# Adafruit_TSSP77038_IR_Demodulator_Breako.net
KiCad netlist of a schematic drawn in EAGLE
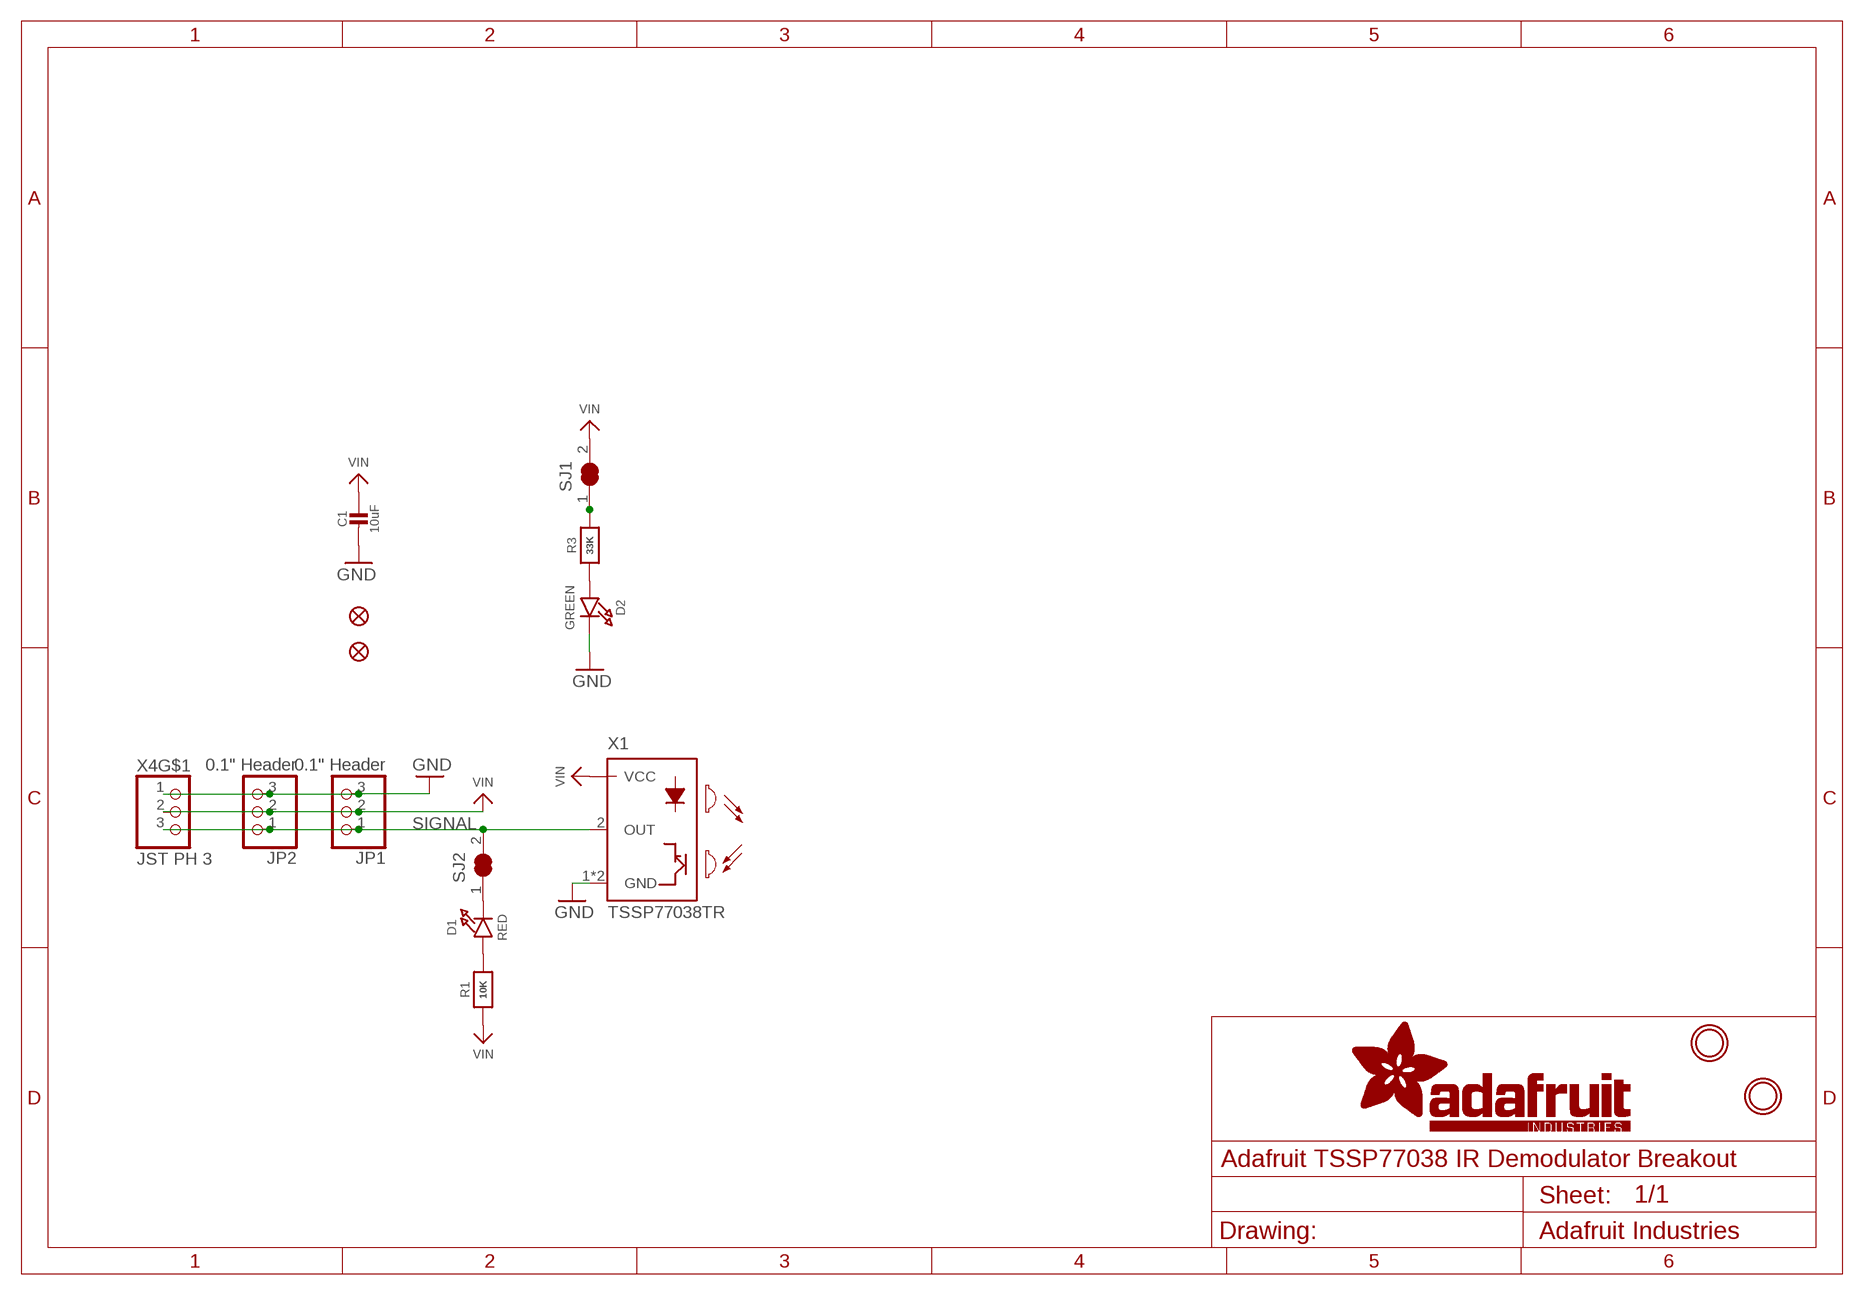
[diagram p0: schematic, sheet 1]

(export (version "E")
  (design (tool "Eeschema 10.0.6"))
  (components
    (comp (ref "C1")
      (value "10uF")
      (footprint "eagle-import:0805-NO")
      (libsource (lib "eagle-import") (part "CAP_CERAMIC0805-NOOUTLINE"))
    )
    (comp (ref "D1")
      (value "RED")
      (footprint "eagle-import:CHIPLED_0603_NOOUTLINE")
      (libsource (lib "eagle-import") (part "LED0603_NOOUTLINE"))
    )
    (comp (ref "D2")
      (value "GREEN")
      (footprint "eagle-import:CHIPLED_0603_NOOUTLINE")
      (libsource (lib "eagle-import") (part "LED0603_NOOUTLINE"))
    )
    (comp (ref "FID2")
      (value "FIDUCIAL_1MM")
      (footprint "eagle-import:FIDUCIAL_1MM")
      (libsource (lib "eagle-import") (part "FIDUCIAL_1MM"))
    )
    (comp (ref "FID3")
      (value "FIDUCIAL_1MM")
      (footprint "eagle-import:FIDUCIAL_1MM")
      (libsource (lib "eagle-import") (part "FIDUCIAL_1MM"))
    )
    (comp (ref "JP1")
      (value "0.1\" Header")
      (footprint "eagle-import:1X03_OVAL")
      (libsource (lib "eagle-import") (part "HEADER-1X3"))
    )
    (comp (ref "JP2")
      (value "0.1\" Header")
      (footprint "eagle-import:1X03_ROUND_76")
      (libsource (lib "eagle-import") (part "HEADER-1X376MIL"))
    )
    (comp (ref "R1")
      (value "10K")
      (footprint "eagle-import:0603-NO")
      (libsource (lib "eagle-import") (part "RESISTOR_0603_NOOUT"))
    )
    (comp (ref "R3")
      (value "33K")
      (footprint "eagle-import:0603-NO")
      (libsource (lib "eagle-import") (part "RESISTOR_0603_NOOUT"))
    )
    (comp (ref "SJ1")
      (value "SOLDERJUMPER_CLOSED")
      (footprint "eagle-import:SOLDERJUMPER_CLOSEDWIRE")
      (libsource (lib "eagle-import") (part "SOLDERJUMPER_CLOSED"))
    )
    (comp (ref "SJ2")
      (value "SOLDERJUMPER_CLOSED")
      (footprint "eagle-import:SOLDERJUMPER_CLOSEDWIRE")
      (libsource (lib "eagle-import") (part "SOLDERJUMPER_CLOSED"))
    )
    (comp (ref "U$1")
      (value "MOUNTINGHOLE2.5")
      (footprint "eagle-import:MOUNTINGHOLE_2.5_PLATED")
      (libsource (lib "eagle-import") (part "MOUNTINGHOLE2.5"))
    )
    (comp (ref "U$8")
      (value "MOUNTINGHOLE2.5")
      (footprint "eagle-import:MOUNTINGHOLE_2.5_PLATED")
      (libsource (lib "eagle-import") (part "MOUNTINGHOLE2.5"))
    )
    (comp (ref "X1")
      (value "TSSP77038TR")
      (footprint "eagle-import:VEML7700")
      (libsource (lib "eagle-import") (part "TSSP770XXTR"))
    )
    (comp (ref "X4")
      (value "JST PH 3")
      (footprint "eagle-import:JSTPH3")
      (libsource (lib "eagle-import") (part "CON_JST_PH_3PIN"))
    )
  )
  (nets
    (net (code "1") (name "/SIGNAL") (class "Default")
      (node (ref "JP1") (pin "1") (pinfunction "1_1") (pintype "passive"))
      (node (ref "JP2") (pin "1") (pinfunction "1_1") (pintype "passive"))
      (node (ref "SJ2") (pin "2") (pinfunction "2_2") (pintype "passive"))
      (node (ref "X1") (pin "2") (pinfunction "OUT_2") (pintype "output"))
      (node (ref "X4") (pin "3") (pinfunction "3_3") (pintype "passive"))
    )
    (net (code "2") (name "GND") (class "Default")
      (node (ref "C1") (pin "2") (pinfunction "2_2") (pintype "passive"))
      (node (ref "D2") (pin "C") (pinfunction "C_C") (pintype "passive"))
      (node (ref "JP1") (pin "3") (pinfunction "3_3") (pintype "passive"))
      (node (ref "JP2") (pin "3") (pinfunction "3_3") (pintype "passive"))
      (node (ref "X1") (pin "1") (pinfunction "GND_1") (pintype "power_in"))
      (node (ref "X1") (pin "4") (pinfunction "GND_4") (pintype "power_in"))
      (node (ref "X4") (pin "1") (pinfunction "1_1") (pintype "passive"))
    )
    (net (code "3") (name "Net-(D1-PadA)") (class "Default")
      (node (ref "D1") (pin "A") (pinfunction "A_A") (pintype "passive"))
      (node (ref "R1") (pin "2") (pinfunction "2_2") (pintype "passive"))
    )
    (net (code "4") (name "Net-(D1-PadC)") (class "Default")
      (node (ref "D1") (pin "C") (pinfunction "C_C") (pintype "passive"))
      (node (ref "SJ2") (pin "1") (pinfunction "1_1") (pintype "passive"))
    )
    (net (code "5") (name "Net-(D2-PadA)") (class "Default")
      (node (ref "D2") (pin "A") (pinfunction "A_A") (pintype "passive"))
      (node (ref "R3") (pin "1") (pinfunction "1_1") (pintype "passive"))
    )
    (net (code "6") (name "Net-(R3-Pad2)") (class "Default")
      (node (ref "R3") (pin "2") (pinfunction "2_2") (pintype "passive"))
      (node (ref "SJ1") (pin "1") (pinfunction "1_1") (pintype "passive"))
    )
    (net (code "7") (name "VIN") (class "Default")
      (node (ref "C1") (pin "1") (pinfunction "1_1") (pintype "passive"))
      (node (ref "JP1") (pin "2") (pinfunction "2_2") (pintype "passive"))
      (node (ref "JP2") (pin "2") (pinfunction "2_2") (pintype "passive"))
      (node (ref "R1") (pin "1") (pinfunction "1_1") (pintype "passive"))
      (node (ref "SJ1") (pin "2") (pinfunction "2_2") (pintype "passive"))
      (node (ref "X1") (pin "3") (pinfunction "VCC_3") (pintype "power_in"))
      (node (ref "X4") (pin "2") (pinfunction "2_2") (pintype "passive"))
    )
  )
)
